# SCH_MPU_GPS_LORA_bmp_rstbtn_test_2022-12.net
KiCad netlist of a schematic drawn in EasyEDA
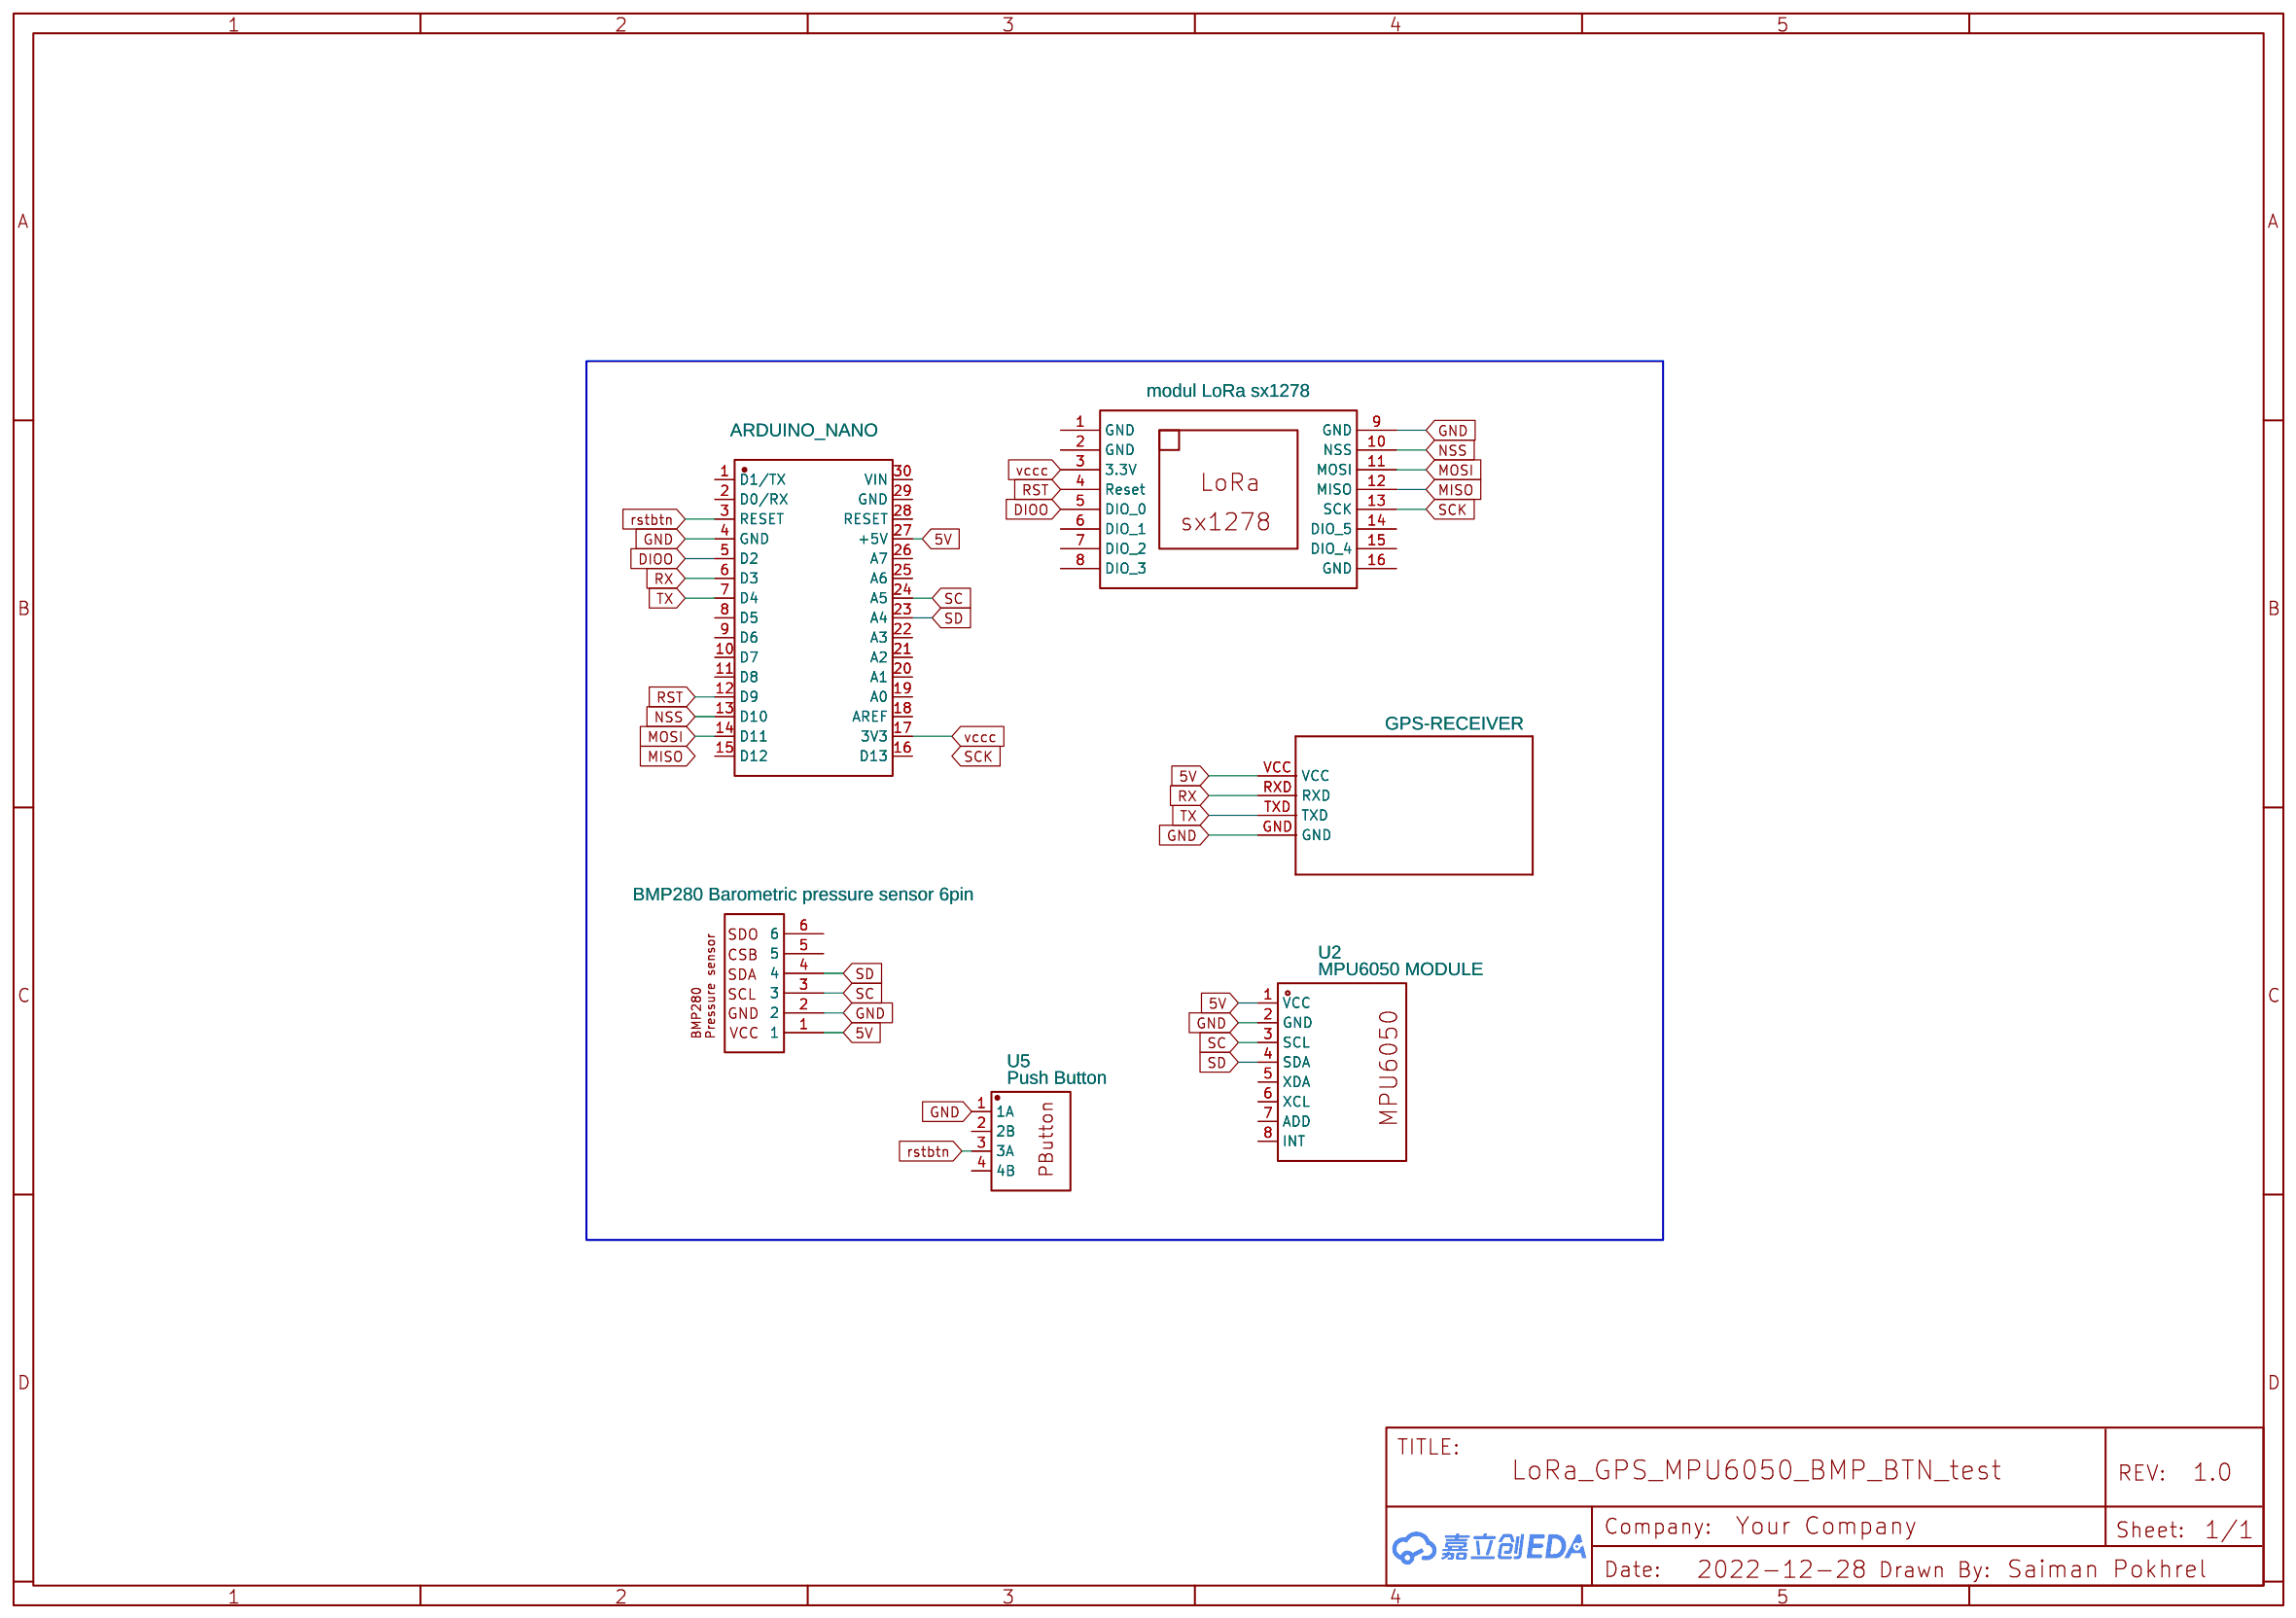
[diagram p0: schematic sheet]

(export (version "E")
  (design (tool "Eeschema 10.0.6"))
  (components
    (comp (ref "1") (value "GPS-RECEIVER") (libsource (lib "") (part "GPS-RECEIVER-NEO8M")))
    (comp (ref "U1")
      (value "BMP280 Barometric pressure sensor 6pin")
      (fields (field (name "BOM_Manufacturer Part") "MAX6675"))
      (libsource (lib "") (part "BMP280 Barometric pressure sensor 6pin"))
    )
    (comp (ref "U2")
      (value "MPU6050 MODULE")
      (fields (field (name "BOM_Manufacturer Part") "MPU6050"))
      (libsource (lib "") (part "MPU6050 MODULE"))
    )
    (comp (ref "U3") (value "modul LoRa sx1278") (libsource (lib "") (part "modul LoRa sx1278")))
    (comp (ref "U4")
      (value "ARDUINO_NANO")
      (fields (field (name "BOM_Supplier Part") "C9900017879"))
      (libsource (lib "") (part "ARDUINO_NANO"))
    )
    (comp (ref "U5") (value "Push Button") (libsource (lib "") (part "Push Button")))
  )
  (nets
    (net (code "1") (name "5V") (class "Default")
      (node (ref "1") (pin "VCC") (pinfunction "VCC_VCC") (pintype "bidirectional"))
      (node (ref "U1") (pin "1") (pinfunction "1_1") (pintype "unspecified"))
      (node (ref "U2") (pin "1") (pinfunction "VCC_1") (pintype "passive"))
      (node (ref "U4") (pin "27") (pinfunction "+5V_27") (pintype "unspecified"))
    )
    (net (code "2") (name "DIOO") (class "Default")
      (node (ref "U3") (pin "5") (pinfunction "DIO_0_5") (pintype "bidirectional"))
      (node (ref "U4") (pin "5") (pinfunction "D2_5") (pintype "unspecified"))
    )
    (net (code "3") (name "GND") (class "Default")
      (node (ref "1") (pin "GND") (pinfunction "GND_GND") (pintype "bidirectional"))
      (node (ref "U1") (pin "2") (pinfunction "2_2") (pintype "unspecified"))
      (node (ref "U2") (pin "2") (pinfunction "GND_2") (pintype "passive"))
      (node (ref "U3") (pin "9") (pinfunction "GND_9") (pintype "unspecified"))
      (node (ref "U4") (pin "4") (pinfunction "GND_4") (pintype "unspecified"))
      (node (ref "U5") (pin "1") (pinfunction "1A_1") (pintype "unspecified"))
    )
    (net (code "4") (name "MISO") (class "Default")
      (node (ref "U3") (pin "12") (pinfunction "MISO_12") (pintype "output"))
    )
    (net (code "5") (name "MOSI") (class "Default")
      (node (ref "U3") (pin "11") (pinfunction "MOSI_11") (pintype "input"))
      (node (ref "U4") (pin "14") (pinfunction "D11_14") (pintype "unspecified"))
    )
    (net (code "6") (name "NSS") (class "Default")
      (node (ref "U3") (pin "10") (pinfunction "NSS_10") (pintype "unspecified"))
      (node (ref "U4") (pin "13") (pinfunction "D10_13") (pintype "unspecified"))
    )
    (net (code "7") (name "RST") (class "Default")
      (node (ref "U3") (pin "4") (pinfunction "Reset_4") (pintype "unspecified"))
      (node (ref "U4") (pin "12") (pinfunction "D9_12") (pintype "unspecified"))
    )
    (net (code "8") (name "RX") (class "Default")
      (node (ref "1") (pin "RXD") (pinfunction "RXD_RXD") (pintype "bidirectional"))
      (node (ref "U4") (pin "6") (pinfunction "D3_6") (pintype "unspecified"))
    )
    (net (code "9") (name "SC") (class "Default")
      (node (ref "U1") (pin "3") (pinfunction "3_3") (pintype "unspecified"))
      (node (ref "U2") (pin "3") (pinfunction "SCL_3") (pintype "input"))
      (node (ref "U4") (pin "24") (pinfunction "A5_24") (pintype "unspecified"))
    )
    (net (code "10") (name "SCK") (class "Default")
      (node (ref "U3") (pin "13") (pinfunction "SCK_13") (pintype "unspecified"))
    )
    (net (code "11") (name "SD") (class "Default")
      (node (ref "U1") (pin "4") (pinfunction "4_4") (pintype "unspecified"))
      (node (ref "U2") (pin "4") (pinfunction "SDA_4") (pintype "bidirectional"))
      (node (ref "U4") (pin "23") (pinfunction "A4_23") (pintype "unspecified"))
    )
    (net (code "12") (name "TX") (class "Default")
      (node (ref "1") (pin "TXD") (pinfunction "TXD_TXD") (pintype "bidirectional"))
      (node (ref "U4") (pin "7") (pinfunction "D4_7") (pintype "unspecified"))
    )
    (net (code "13") (name "rstbtn") (class "Default")
      (node (ref "U4") (pin "3") (pinfunction "RESET_3") (pintype "unspecified"))
      (node (ref "U5") (pin "3") (pinfunction "3A_3") (pintype "unspecified"))
    )
    (net (code "14") (name "unconnected-(U1-Pad5)") (class "Default")
      (node (ref "U1") (pin "5") (pinfunction "5_5") (pintype "unspecified"))
    )
    (net (code "15") (name "unconnected-(U1-Pad6)") (class "Default")
      (node (ref "U1") (pin "6") (pinfunction "6_6") (pintype "unspecified"))
    )
    (net (code "16") (name "unconnected-(U2-ADD-Pad7)") (class "Default")
      (node (ref "U2") (pin "7") (pinfunction "ADD_7") (pintype "unspecified"))
    )
    (net (code "17") (name "unconnected-(U2-INT-Pad8)") (class "Default")
      (node (ref "U2") (pin "8") (pinfunction "INT_8") (pintype "unspecified"))
    )
    (net (code "18") (name "unconnected-(U2-XCL-Pad6)") (class "Default")
      (node (ref "U2") (pin "6") (pinfunction "XCL_6") (pintype "input"))
    )
    (net (code "19") (name "unconnected-(U2-XDA-Pad5)") (class "Default")
      (node (ref "U2") (pin "5") (pinfunction "XDA_5") (pintype "bidirectional"))
    )
    (net (code "20") (name "unconnected-(U3-DIO_1-Pad6)") (class "Default")
      (node (ref "U3") (pin "6") (pinfunction "DIO_1_6") (pintype "bidirectional"))
    )
    (net (code "21") (name "unconnected-(U3-DIO_2-Pad7)") (class "Default")
      (node (ref "U3") (pin "7") (pinfunction "DIO_2_7") (pintype "bidirectional"))
    )
    (net (code "22") (name "unconnected-(U3-DIO_3-Pad8)") (class "Default")
      (node (ref "U3") (pin "8") (pinfunction "DIO_3_8") (pintype "bidirectional"))
    )
    (net (code "23") (name "unconnected-(U3-DIO_4-Pad15)") (class "Default")
      (node (ref "U3") (pin "15") (pinfunction "DIO_4_15") (pintype "bidirectional"))
    )
    (net (code "24") (name "unconnected-(U3-DIO_5-Pad14)") (class "Default")
      (node (ref "U3") (pin "14") (pinfunction "DIO_5_14") (pintype "bidirectional"))
    )
    (net (code "25") (name "unconnected-(U3-GND-Pad1)") (class "Default")
      (node (ref "U3") (pin "1") (pinfunction "GND_1") (pintype "unspecified"))
    )
    (net (code "26") (name "unconnected-(U3-GND-Pad2)") (class "Default")
      (node (ref "U3") (pin "2") (pinfunction "GND_2") (pintype "unspecified"))
    )
    (net (code "27") (name "unconnected-(U3-GND-Pad16)") (class "Default")
      (node (ref "U3") (pin "16") (pinfunction "GND_16") (pintype "unspecified"))
    )
    (net (code "28") (name "unconnected-(U4-A0-Pad19)") (class "Default")
      (node (ref "U4") (pin "19") (pinfunction "A0_19") (pintype "unspecified"))
    )
    (net (code "29") (name "unconnected-(U4-A1-Pad20)") (class "Default")
      (node (ref "U4") (pin "20") (pinfunction "A1_20") (pintype "unspecified"))
    )
    (net (code "30") (name "unconnected-(U4-A2-Pad21)") (class "Default")
      (node (ref "U4") (pin "21") (pinfunction "A2_21") (pintype "unspecified"))
    )
    (net (code "31") (name "unconnected-(U4-A3-Pad22)") (class "Default")
      (node (ref "U4") (pin "22") (pinfunction "A3_22") (pintype "unspecified"))
    )
    (net (code "32") (name "unconnected-(U4-A6-Pad25)") (class "Default")
      (node (ref "U4") (pin "25") (pinfunction "A6_25") (pintype "unspecified"))
    )
    (net (code "33") (name "unconnected-(U4-A7-Pad26)") (class "Default")
      (node (ref "U4") (pin "26") (pinfunction "A7_26") (pintype "unspecified"))
    )
    (net (code "34") (name "unconnected-(U4-AREF-Pad18)") (class "Default")
      (node (ref "U4") (pin "18") (pinfunction "AREF_18") (pintype "unspecified"))
    )
    (net (code "35") (name "unconnected-(U4-D0{slash}RX-Pad2)") (class "Default")
      (node (ref "U4") (pin "2") (pinfunction "D0/RX_2") (pintype "unspecified"))
    )
    (net (code "36") (name "unconnected-(U4-D1{slash}TX-Pad1)") (class "Default")
      (node (ref "U4") (pin "1") (pinfunction "D1/TX_1") (pintype "unspecified"))
    )
    (net (code "37") (name "unconnected-(U4-D5-Pad8)") (class "Default")
      (node (ref "U4") (pin "8") (pinfunction "D5_8") (pintype "unspecified"))
    )
    (net (code "38") (name "unconnected-(U4-D6-Pad9)") (class "Default")
      (node (ref "U4") (pin "9") (pinfunction "D6_9") (pintype "unspecified"))
    )
    (net (code "39") (name "unconnected-(U4-D7-Pad10)") (class "Default")
      (node (ref "U4") (pin "10") (pinfunction "D7_10") (pintype "unspecified"))
    )
    (net (code "40") (name "unconnected-(U4-D8-Pad11)") (class "Default")
      (node (ref "U4") (pin "11") (pinfunction "D8_11") (pintype "unspecified"))
    )
    (net (code "41") (name "unconnected-(U4-D12-Pad15)") (class "Default")
      (node (ref "U4") (pin "15") (pinfunction "D12_15") (pintype "unspecified"))
    )
    (net (code "42") (name "unconnected-(U4-D13-Pad16)") (class "Default")
      (node (ref "U4") (pin "16") (pinfunction "D13_16") (pintype "unspecified"))
    )
    (net (code "43") (name "unconnected-(U4-GND-Pad29)") (class "Default")
      (node (ref "U4") (pin "29") (pinfunction "GND_29") (pintype "unspecified"))
    )
    (net (code "44") (name "unconnected-(U4-RESET-Pad28)") (class "Default")
      (node (ref "U4") (pin "28") (pinfunction "RESET_28") (pintype "unspecified"))
    )
    (net (code "45") (name "unconnected-(U4-VIN-Pad30)") (class "Default")
      (node (ref "U4") (pin "30") (pinfunction "VIN_30") (pintype "unspecified"))
    )
    (net (code "46") (name "unconnected-(U5-2B-Pad2)") (class "Default")
      (node (ref "U5") (pin "2") (pinfunction "2B_2") (pintype "unspecified"))
    )
    (net (code "47") (name "unconnected-(U5-4B-Pad4)") (class "Default")
      (node (ref "U5") (pin "4") (pinfunction "4B_4") (pintype "unspecified"))
    )
    (net (code "48") (name "vccc") (class "Default")
      (node (ref "U3") (pin "3") (pinfunction "3.3V_3") (pintype "passive"))
      (node (ref "U4") (pin "17") (pinfunction "3V3_17") (pintype "unspecified"))
    )
  )
)
